# Controller.net
KiCad netlist of a schematic drawn in EAGLE
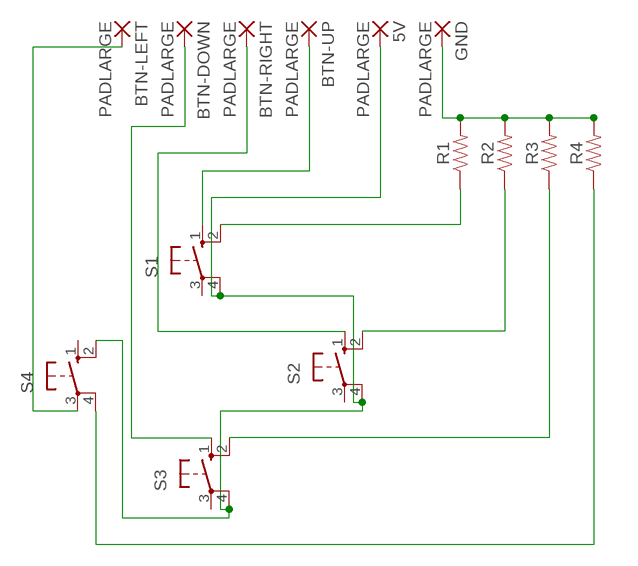
[diagram p0: schematic, sheet 1]

(export (version "E")
  (design (tool "Eeschema 10.0.6"))
  (components
    (comp (ref "5V")
      (value "PADLARGE")
      (footprint "eagle-import:SMDLARGE")
      (libsource (lib "eagle-import") (part "PADLARGE"))
    )
    (comp (ref "BTN-DOWN")
      (value "PADLARGE")
      (footprint "eagle-import:SMDLARGE")
      (libsource (lib "eagle-import") (part "PADLARGE"))
    )
    (comp (ref "BTN-LEFT")
      (value "PADLARGE")
      (footprint "eagle-import:SMDLARGE")
      (libsource (lib "eagle-import") (part "PADLARGE"))
    )
    (comp (ref "BTN-RIGHT")
      (value "PADLARGE")
      (footprint "eagle-import:SMDLARGE")
      (libsource (lib "eagle-import") (part "PADLARGE"))
    )
    (comp (ref "BTN-UP")
      (value "PADLARGE")
      (footprint "eagle-import:SMDLARGE")
      (libsource (lib "eagle-import") (part "PADLARGE"))
    )
    (comp (ref "GND")
      (value "PADLARGE")
      (footprint "eagle-import:SMDLARGE")
      (libsource (lib "eagle-import") (part "PADLARGE"))
    )
    (comp (ref "R1")
      (value "RESISTORAXIAL-0.3")
      (footprint "eagle-import:AXIAL-0.3")
      (libsource (lib "eagle-import") (part "RESISTORAXIAL-0.3"))
    )
    (comp (ref "R2")
      (value "RESISTORAXIAL-0.3")
      (footprint "eagle-import:AXIAL-0.3")
      (libsource (lib "eagle-import") (part "RESISTORAXIAL-0.3"))
    )
    (comp (ref "R3")
      (value "RESISTORAXIAL-0.3")
      (footprint "eagle-import:AXIAL-0.3")
      (libsource (lib "eagle-import") (part "RESISTORAXIAL-0.3"))
    )
    (comp (ref "R4")
      (value "RESISTORAXIAL-0.3")
      (footprint "eagle-import:AXIAL-0.3")
      (libsource (lib "eagle-import") (part "RESISTORAXIAL-0.3"))
    )
    (comp (ref "S1")
      (value "10-XX")
      (footprint "eagle-import:B3F-10XX")
      (fields (field (name "MPN") "B3F-1000"))
      (libsource (lib "eagle-import") (part "10-XX"))
    )
    (comp (ref "S2")
      (value "10-XX")
      (footprint "eagle-import:B3F-10XX")
      (fields (field (name "MPN") "B3F-1000"))
      (libsource (lib "eagle-import") (part "10-XX"))
    )
    (comp (ref "S3")
      (value "10-XX")
      (footprint "eagle-import:B3F-10XX")
      (fields (field (name "MPN") "B3F-1000"))
      (libsource (lib "eagle-import") (part "10-XX"))
    )
    (comp (ref "S4")
      (value "10-XX")
      (footprint "eagle-import:B3F-10XX")
      (fields (field (name "MPN") "B3F-1000"))
      (libsource (lib "eagle-import") (part "10-XX"))
    )
  )
  (nets
    (net (code "1") (name "Net-(5V-P)") (class "Default")
      (node (ref "5V") (pin "P$1") (pinfunction "P_P$1") (pintype "passive"))
      (node (ref "S1") (pin "4") (pinfunction "P1_4") (pintype "passive"))
      (node (ref "S2") (pin "4") (pinfunction "P1_4") (pintype "passive"))
      (node (ref "S3") (pin "4") (pinfunction "P1_4") (pintype "passive"))
      (node (ref "S4") (pin "2") (pinfunction "S1_2") (pintype "passive"))
    )
    (net (code "2") (name "Net-(BTN-DOWN-P)") (class "Default")
      (node (ref "BTN-DOWN") (pin "P$1") (pinfunction "P_P$1") (pintype "passive"))
      (node (ref "S3") (pin "1") (pinfunction "S_1") (pintype "passive"))
    )
    (net (code "3") (name "Net-(BTN-LEFT-P)") (class "Default")
      (node (ref "BTN-LEFT") (pin "P$1") (pinfunction "P_P$1") (pintype "passive"))
      (node (ref "S4") (pin "3") (pinfunction "P_3") (pintype "passive"))
    )
    (net (code "4") (name "Net-(BTN-RIGHT-P)") (class "Default")
      (node (ref "BTN-RIGHT") (pin "P$1") (pinfunction "P_P$1") (pintype "passive"))
      (node (ref "S2") (pin "1") (pinfunction "S_1") (pintype "passive"))
    )
    (net (code "5") (name "Net-(BTN-UP-P)") (class "Default")
      (node (ref "BTN-UP") (pin "P$1") (pinfunction "P_P$1") (pintype "passive"))
      (node (ref "S1") (pin "1") (pinfunction "S_1") (pintype "passive"))
    )
    (net (code "6") (name "Net-(GND-P)") (class "Default")
      (node (ref "GND") (pin "P$1") (pinfunction "P_P$1") (pintype "passive"))
      (node (ref "R1") (pin "P$2") (pinfunction "2_P$2") (pintype "passive"))
      (node (ref "R2") (pin "P$2") (pinfunction "2_P$2") (pintype "passive"))
      (node (ref "R3") (pin "P$2") (pinfunction "2_P$2") (pintype "passive"))
      (node (ref "R4") (pin "P$2") (pinfunction "2_P$2") (pintype "passive"))
    )
    (net (code "7") (name "Net-(R1-1)") (class "Default")
      (node (ref "R1") (pin "P$1") (pinfunction "1_P$1") (pintype "passive"))
      (node (ref "S1") (pin "2") (pinfunction "S1_2") (pintype "passive"))
    )
    (net (code "8") (name "Net-(R2-1)") (class "Default")
      (node (ref "R2") (pin "P$1") (pinfunction "1_P$1") (pintype "passive"))
      (node (ref "S2") (pin "2") (pinfunction "S1_2") (pintype "passive"))
    )
    (net (code "9") (name "Net-(R3-1)") (class "Default")
      (node (ref "R3") (pin "P$1") (pinfunction "1_P$1") (pintype "passive"))
      (node (ref "S3") (pin "2") (pinfunction "S1_2") (pintype "passive"))
    )
    (net (code "10") (name "Net-(R4-1)") (class "Default")
      (node (ref "R4") (pin "P$1") (pinfunction "1_P$1") (pintype "passive"))
      (node (ref "S4") (pin "4") (pinfunction "P1_4") (pintype "passive"))
    )
    (net (code "11") (name "unconnected-(S1-P-Pad3)") (class "Default")
      (node (ref "S1") (pin "3") (pinfunction "P_3") (pintype "passive"))
    )
    (net (code "12") (name "unconnected-(S2-P-Pad3)") (class "Default")
      (node (ref "S2") (pin "3") (pinfunction "P_3") (pintype "passive"))
    )
    (net (code "13") (name "unconnected-(S3-P-Pad3)") (class "Default")
      (node (ref "S3") (pin "3") (pinfunction "P_3") (pintype "passive"))
    )
    (net (code "14") (name "unconnected-(S4-S-Pad1)") (class "Default")
      (node (ref "S4") (pin "1") (pinfunction "S_1") (pintype "passive"))
    )
  )
)
